# MUV_gas_pcb.net
KiCad netlist of a schematic drawn in EAGLE
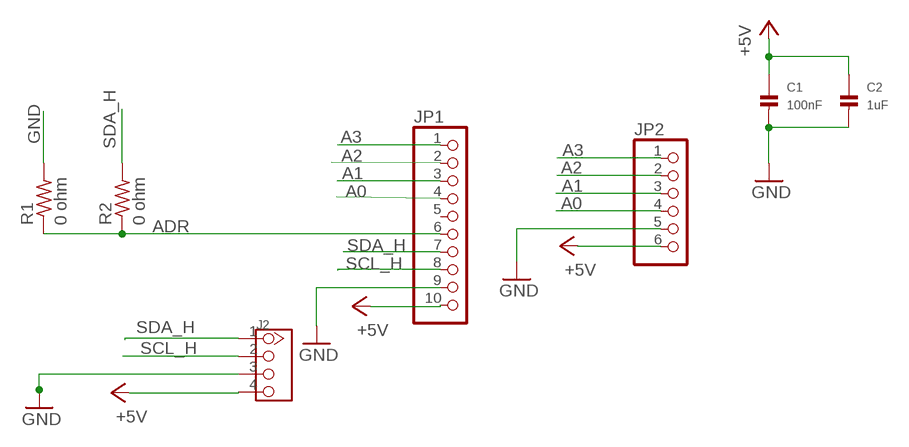
[diagram p0: schematic, sheet 1]

(export (version "E")
  (design (tool "Eeschema 10.0.6"))
  (components
    (comp (ref "C1")
      (value "100nF")
      (footprint "eagle-import:1206")
      (libsource (lib "eagle-import") (part "CAP_CERAMIC1206"))
    )
    (comp (ref "C2")
      (value "1uF")
      (footprint "eagle-import:1206")
      (libsource (lib "eagle-import") (part "CAP_CERAMIC1206"))
    )
    (comp (ref "J2")
      (value "TWIG-4P-2.0-2.0")
      (footprint "eagle-import:4P-2.0")
      (libsource (lib "eagle-import") (part "TWIG-4P-2.0-2.0"))
    )
    (comp (ref "JP1")
      (value "HEADER-1X10")
      (footprint "eagle-import:1X10_OVAL")
      (libsource (lib "eagle-import") (part "HEADER-1X10"))
    )
    (comp (ref "JP2")
      (value "HEADER-1X6")
      (footprint "eagle-import:1X06_OVAL")
      (libsource (lib "eagle-import") (part "HEADER-1X6"))
    )
    (comp (ref "R1")
      (value "0 ohm")
      (footprint "eagle-import:1206")
      (libsource (lib "eagle-import") (part "RESISTOR1206"))
    )
    (comp (ref "R2")
      (value "0 ohm")
      (footprint "eagle-import:1206")
      (libsource (lib "eagle-import") (part "RESISTOR1206"))
    )
  )
  (nets
    (net (code "1") (name "+5V") (class "Default")
      (node (ref "C1") (pin "1") (pinfunction "P$1_1") (pintype "passive"))
      (node (ref "C2") (pin "1") (pinfunction "P$1_1") (pintype "passive"))
      (node (ref "J2") (pin "4") (pinfunction "4_4") (pintype "bidirectional"))
      (node (ref "JP1") (pin "10") (pinfunction "10_10") (pintype "passive"))
      (node (ref "JP2") (pin "6") (pinfunction "6_6") (pintype "passive"))
    )
    (net (code "2") (name "/A0") (class "Default")
      (node (ref "JP1") (pin "4") (pinfunction "4_4") (pintype "passive"))
      (node (ref "JP2") (pin "4") (pinfunction "4_4") (pintype "passive"))
    )
    (net (code "3") (name "/A1") (class "Default")
      (node (ref "JP1") (pin "3") (pinfunction "3_3") (pintype "passive"))
      (node (ref "JP2") (pin "3") (pinfunction "3_3") (pintype "passive"))
    )
    (net (code "4") (name "/A2") (class "Default")
      (node (ref "JP1") (pin "2") (pinfunction "2_2") (pintype "passive"))
      (node (ref "JP2") (pin "2") (pinfunction "2_2") (pintype "passive"))
    )
    (net (code "5") (name "/A3") (class "Default")
      (node (ref "JP1") (pin "1") (pinfunction "1_1") (pintype "passive"))
      (node (ref "JP2") (pin "1") (pinfunction "1_1") (pintype "passive"))
    )
    (net (code "6") (name "/ADR") (class "Default")
      (node (ref "JP1") (pin "6") (pinfunction "6_6") (pintype "passive"))
      (node (ref "R1") (pin "1") (pinfunction "1_1") (pintype "passive"))
      (node (ref "R2") (pin "1") (pinfunction "1_1") (pintype "passive"))
    )
    (net (code "7") (name "/SCL_H") (class "Default")
      (node (ref "J2") (pin "2") (pinfunction "2_2") (pintype "bidirectional"))
      (node (ref "JP1") (pin "8") (pinfunction "8_8") (pintype "passive"))
    )
    (net (code "8") (name "/SDA_H") (class "Default")
      (node (ref "J2") (pin "1") (pinfunction "1_1") (pintype "bidirectional"))
      (node (ref "JP1") (pin "7") (pinfunction "7_7") (pintype "passive"))
      (node (ref "R2") (pin "2") (pinfunction "2_2") (pintype "passive"))
    )
    (net (code "9") (name "GND") (class "Default")
      (node (ref "C1") (pin "2") (pinfunction "P$2_2") (pintype "passive"))
      (node (ref "C2") (pin "2") (pinfunction "P$2_2") (pintype "passive"))
      (node (ref "J2") (pin "3") (pinfunction "3_3") (pintype "bidirectional"))
      (node (ref "JP1") (pin "9") (pinfunction "9_9") (pintype "passive"))
      (node (ref "JP2") (pin "5") (pinfunction "5_5") (pintype "passive"))
      (node (ref "R1") (pin "2") (pinfunction "2_2") (pintype "passive"))
    )
    (net (code "10") (name "unconnected-(JP1-Pad5)") (class "Default")
      (node (ref "JP1") (pin "5") (pinfunction "5_5") (pintype "passive"))
    )
  )
)
